# working.net
KiCad netlist of a schematic drawn in EAGLE
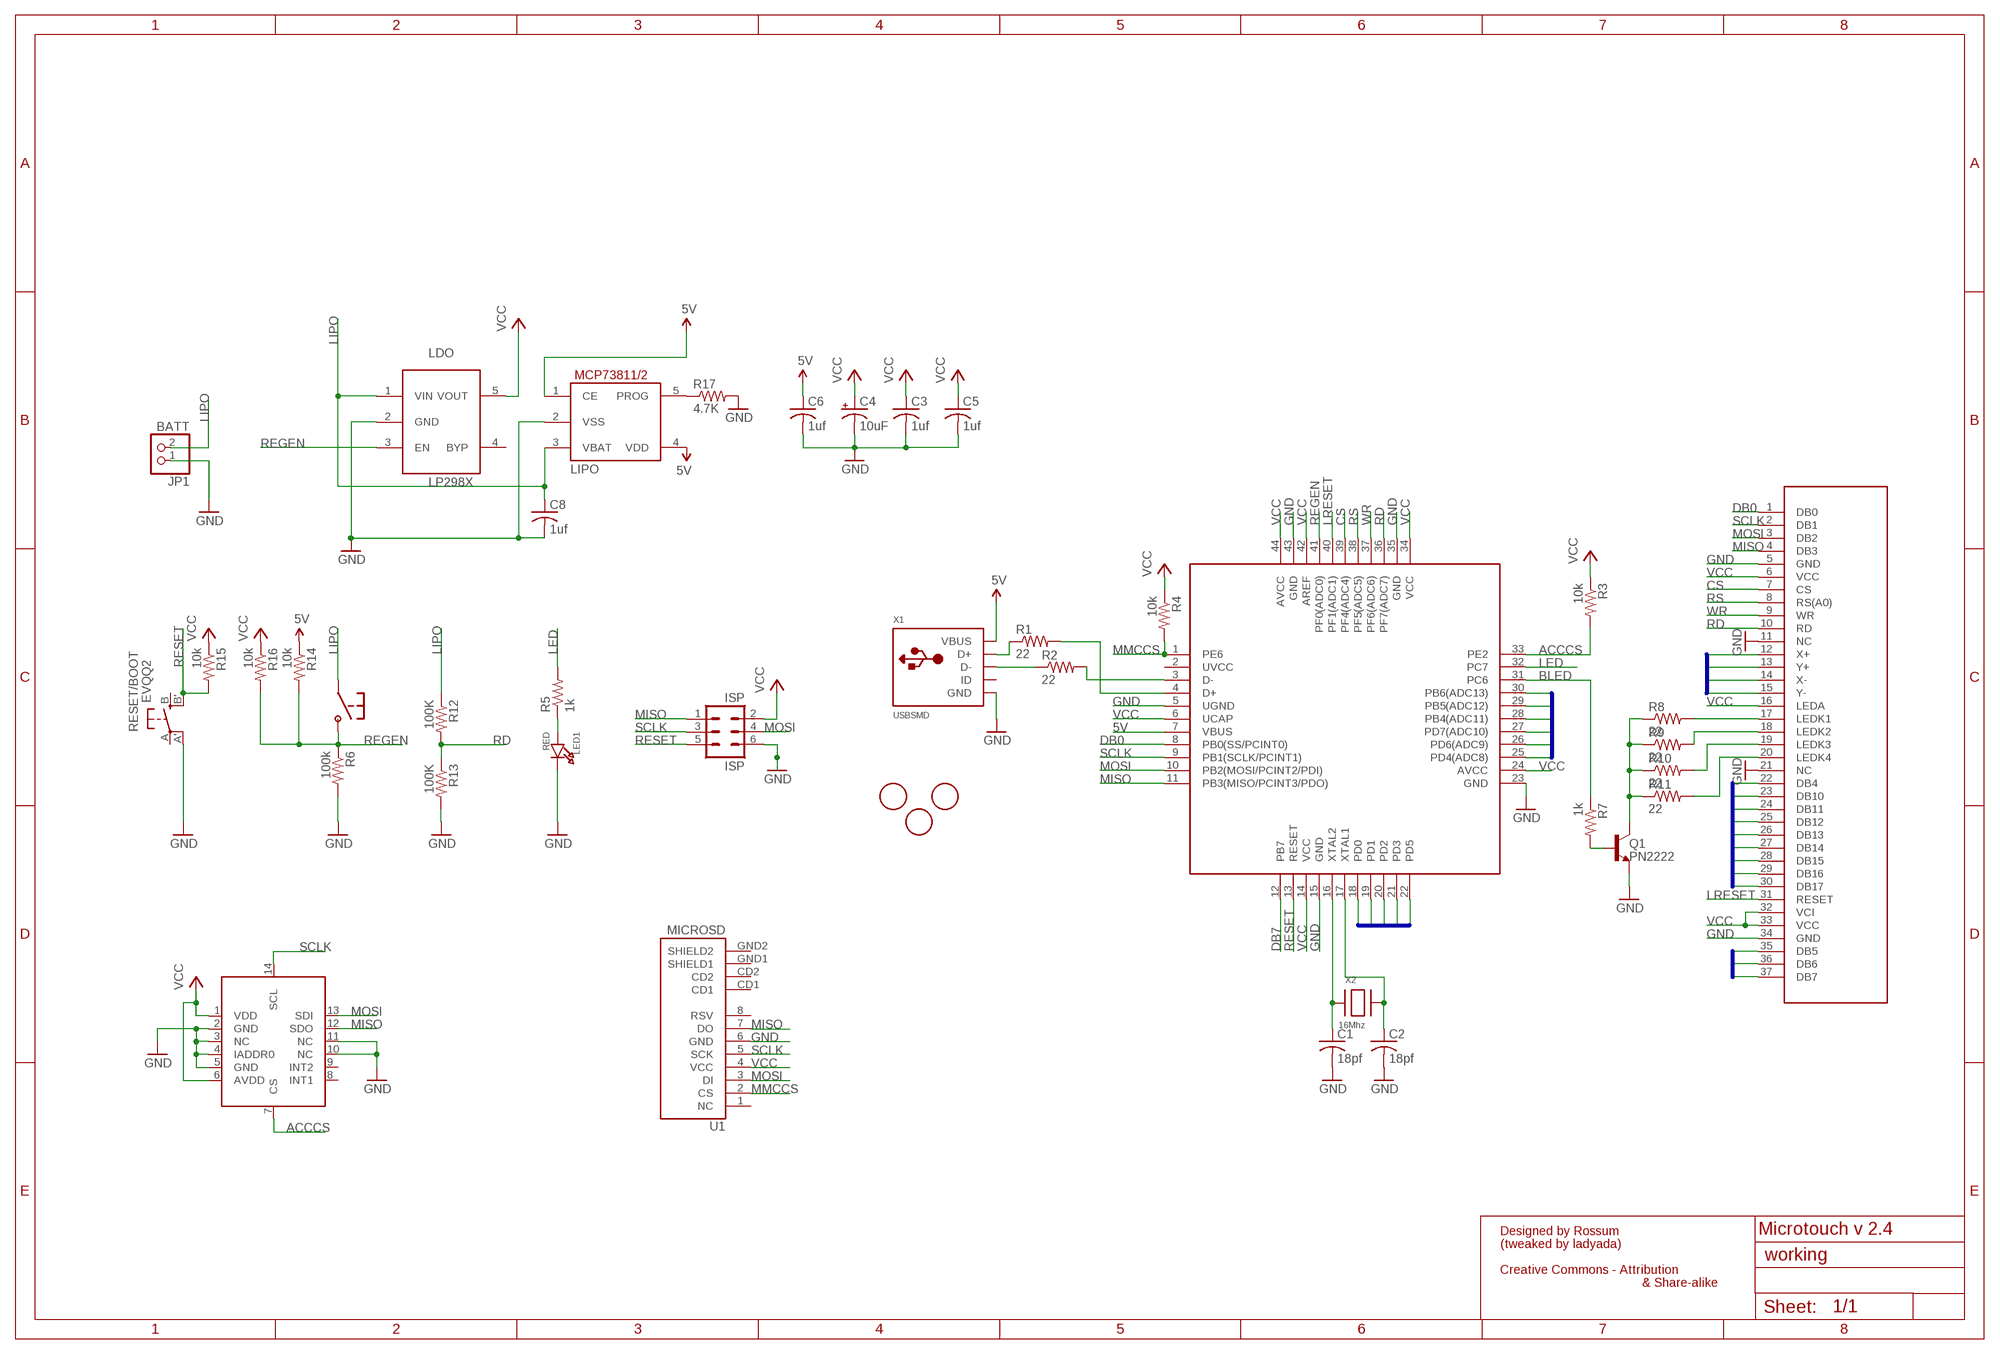
[diagram p0: schematic, sheet 1]

(export (version "E")
  (design (tool "Eeschema 10.0.6"))
  (components
    (comp (ref "ACCELEROMERTER")
      (value "MMA7455")
      (footprint "eagle-import:LGA")
      (libsource (lib "eagle-import") (part "MMA7455"))
    )
    (comp (ref "C1")
      (value "18pf")
      (footprint "eagle-import:C0805K")
      (libsource (lib "eagle-import") (part "C-USC0805K"))
    )
    (comp (ref "C2")
      (value "18pf")
      (footprint "eagle-import:C0805K")
      (libsource (lib "eagle-import") (part "C-USC0805K"))
    )
    (comp (ref "C3")
      (value "1uf")
      (footprint "eagle-import:C0805K")
      (libsource (lib "eagle-import") (part "C-USC0805K"))
    )
    (comp (ref "C4")
      (value "10uF")
      (footprint "eagle-import:A_3216-18R")
      (libsource (lib "eagle-import") (part "CPOL-USA/3216-18R"))
    )
    (comp (ref "C5")
      (value "1uf")
      (footprint "eagle-import:C0805K")
      (libsource (lib "eagle-import") (part "C-USC0805K"))
    )
    (comp (ref "C6")
      (value "1uf")
      (footprint "eagle-import:C0805K")
      (libsource (lib "eagle-import") (part "C-USC0805K"))
    )
    (comp (ref "C8")
      (value "1uf")
      (footprint "eagle-import:C0805K")
      (libsource (lib "eagle-import") (part "C-USC0805K"))
    )
    (comp (ref "ISP")
      (value "ISP")
      (footprint "eagle-import:MA03-2")
      (libsource (lib "eagle-import") (part "MA03-2"))
    )
    (comp (ref "JP1")
      (value "BATT")
      (footprint "eagle-import:JSTPH2")
      (libsource (lib "eagle-import") (part "JST_2PIN"))
    )
    (comp (ref "LDO")
      (value "LP298XS")
      (footprint "eagle-import:SOT23-5L")
      (libsource (lib "eagle-import") (part "LP298XS"))
    )
    (comp (ref "LED1")
      (value "RED")
      (footprint "eagle-import:CHIPLED_0805")
      (libsource (lib "eagle-import") (part "LED0805"))
    )
    (comp (ref "LIPO")
      (value "MCP73811/2")
      (footprint "eagle-import:SOT23-5L")
      (libsource (lib "eagle-import") (part "MCP73811/2"))
    )
    (comp (ref "Q1")
      (value "PN2222")
      (footprint "eagle-import:SOT23-BEC")
      (libsource (lib "eagle-import") (part "-NPN-SOT23-BECMMBT2222ALT1"))
    )
    (comp (ref "R1")
      (value "22")
      (footprint "eagle-import:R0805")
      (libsource (lib "eagle-import") (part "R-US_R0805"))
    )
    (comp (ref "R2")
      (value "22")
      (footprint "eagle-import:R0805")
      (libsource (lib "eagle-import") (part "R-US_R0805"))
    )
    (comp (ref "R3")
      (value "10k")
      (footprint "eagle-import:M0805")
      (libsource (lib "eagle-import") (part "R-US_M0805"))
    )
    (comp (ref "R4")
      (value "10k")
      (footprint "eagle-import:R0805")
      (libsource (lib "eagle-import") (part "R-US_R0805"))
    )
    (comp (ref "R5")
      (value "1k")
      (footprint "eagle-import:R0805")
      (libsource (lib "eagle-import") (part "R-US_R0805"))
    )
    (comp (ref "R6")
      (value "100k")
      (footprint "eagle-import:R0805")
      (libsource (lib "eagle-import") (part "R-US_R0805"))
    )
    (comp (ref "R7")
      (value "1k")
      (footprint "eagle-import:R0805")
      (libsource (lib "eagle-import") (part "R-US_R0805"))
    )
    (comp (ref "R8")
      (value "22")
      (footprint "eagle-import:R0805")
      (libsource (lib "eagle-import") (part "R-US_R0805"))
    )
    (comp (ref "R9")
      (value "22")
      (footprint "eagle-import:R0805")
      (libsource (lib "eagle-import") (part "R-US_R0805"))
    )
    (comp (ref "R10")
      (value "22")
      (footprint "eagle-import:R0805")
      (libsource (lib "eagle-import") (part "R-US_R0805"))
    )
    (comp (ref "R11")
      (value "22")
      (footprint "eagle-import:R0805")
      (libsource (lib "eagle-import") (part "R-US_R0805"))
    )
    (comp (ref "R12")
      (value "100K")
      (footprint "eagle-import:M0805")
      (libsource (lib "eagle-import") (part "R-US_M0805"))
    )
    (comp (ref "R13")
      (value "100K")
      (footprint "eagle-import:M0805")
      (libsource (lib "eagle-import") (part "R-US_M0805"))
    )
    (comp (ref "R14")
      (value "10k")
      (footprint "eagle-import:R0805")
      (libsource (lib "eagle-import") (part "R-US_R0805"))
    )
    (comp (ref "R15")
      (value "10k")
      (footprint "eagle-import:M0805")
      (libsource (lib "eagle-import") (part "R-US_M0805"))
    )
    (comp (ref "R16")
      (value "10k")
      (footprint "eagle-import:R0805")
      (libsource (lib "eagle-import") (part "R-US_R0805"))
    )
    (comp (ref "R17")
      (value "4.7K")
      (footprint "eagle-import:M0805")
      (libsource (lib "eagle-import") (part "R-US_M0805"))
    )
    (comp (ref "RESET/BOOT")
      (value "EVQQ2")
      (footprint "eagle-import:EVQ-Q2")
      (libsource (lib "eagle-import") (part "EVQQ2"))
    )
    (comp (ref "U$1")
      (value "ATMEGA32U4")
      (footprint "eagle-import:TQFP44")
      (libsource (lib "eagle-import") (part "ATMEGA32U4TQFP"))
    )
    (comp (ref "U$2")
      (value "LCD37")
      (footprint "eagle-import:LCD371MM")
      (libsource (lib "eagle-import") (part "LCD37"))
    )
    (comp (ref "U$6")
      (value "FIDUCIAL")
      (footprint "eagle-import:FIDUCIAL_1MM")
      (libsource (lib "eagle-import") (part "FIDUCIAL"))
    )
    (comp (ref "U$7")
      (value "FIDUCIAL")
      (footprint "eagle-import:FIDUCIAL_1MM")
      (libsource (lib "eagle-import") (part "FIDUCIAL"))
    )
    (comp (ref "U$8")
      (value "FIDUCIAL")
      (footprint "eagle-import:FIDUCIAL_1MM")
      (libsource (lib "eagle-import") (part "FIDUCIAL"))
    )
    (comp (ref "U1")
      (value "MICROSD")
      (footprint "eagle-import:MICRO-SD-SOCKET-PP")
      (libsource (lib "eagle-import") (part "USD-SOCKETNEW"))
    )
    (comp (ref "U2")
      (value "KSSMINISWITCH")
      (footprint "eagle-import:KSSMINI")
      (libsource (lib "eagle-import") (part "KSSMINISWITCH"))
    )
    (comp (ref "X1")
      (value "USBSMD")
      (footprint "eagle-import:USB-MINIB")
      (libsource (lib "eagle-import") (part "USBMINIB"))
    )
    (comp (ref "X2")
      (value "16Mhz")
      (footprint "eagle-import:NX5032")
      (libsource (lib "eagle-import") (part "XTALNX5032"))
    )
  )
  (nets
    (net (code "1") (name "/ACCCS") (class "Default")
      (node (ref "ACCELEROMERTER") (pin "7") (pinfunction "CS_7") (pintype "bidirectional"))
      (node (ref "R3") (pin "2") (pinfunction "2_2") (pintype "passive"))
      (node (ref "U$1") (pin "33") (pinfunction "PE2_33") (pintype "bidirectional"))
    )
    (net (code "2") (name "/BLED") (class "Default")
      (node (ref "R7") (pin "1") (pinfunction "1_1") (pintype "passive"))
      (node (ref "U$1") (pin "31") (pinfunction "PC6_31") (pintype "bidirectional"))
    )
    (net (code "3") (name "/CS") (class "Default")
      (node (ref "U$1") (pin "39") (pinfunction "PF4(ADC4)_39") (pintype "bidirectional"))
      (node (ref "U$2") (pin "7") (pinfunction "CS_7") (pintype "bidirectional"))
    )
    (net (code "4") (name "/DB0") (class "Default")
      (node (ref "U$1") (pin "8") (pinfunction "PB0(SS/PCINT0)_8") (pintype "bidirectional"))
      (node (ref "U$2") (pin "1") (pinfunction "DB0_1") (pintype "bidirectional"))
    )
    (net (code "5") (name "/DB4") (class "Default")
      (node (ref "U$1") (pin "28") (pinfunction "PB4(ADC11)_28") (pintype "bidirectional"))
      (node (ref "U$2") (pin "12") (pinfunction "X+_12") (pintype "bidirectional"))
      (node (ref "U$2") (pin "22") (pinfunction "DB4_22") (pintype "bidirectional"))
    )
    (net (code "6") (name "/DB5") (class "Default")
      (node (ref "U$1") (pin "29") (pinfunction "PB5(ADC12)_29") (pintype "bidirectional"))
      (node (ref "U$2") (pin "13") (pinfunction "Y+_13") (pintype "bidirectional"))
      (node (ref "U$2") (pin "35") (pinfunction "DB5_35") (pintype "bidirectional"))
    )
    (net (code "7") (name "/DB6") (class "Default")
      (node (ref "U$1") (pin "30") (pinfunction "PB6(ADC13)_30") (pintype "bidirectional"))
      (node (ref "U$2") (pin "36") (pinfunction "DB6_36") (pintype "bidirectional"))
    )
    (net (code "8") (name "/DB7") (class "Default")
      (node (ref "U$1") (pin "12") (pinfunction "PB7_12") (pintype "bidirectional"))
      (node (ref "U$2") (pin "37") (pinfunction "DB7_37") (pintype "bidirectional"))
    )
    (net (code "9") (name "/DB8") (class "Default")
      (node (ref "U$1") (pin "18") (pinfunction "PD0_18") (pintype "bidirectional"))
      (node (ref "U$2") (pin "23") (pinfunction "DB10_23") (pintype "bidirectional"))
    )
    (net (code "10") (name "/DB9") (class "Default")
      (node (ref "U$1") (pin "19") (pinfunction "PD1_19") (pintype "bidirectional"))
      (node (ref "U$2") (pin "24") (pinfunction "DB11_24") (pintype "bidirectional"))
    )
    (net (code "11") (name "/DB10") (class "Default")
      (node (ref "U$1") (pin "20") (pinfunction "PD2_20") (pintype "bidirectional"))
      (node (ref "U$2") (pin "25") (pinfunction "DB12_25") (pintype "bidirectional"))
    )
    (net (code "12") (name "/DB11") (class "Default")
      (node (ref "U$1") (pin "21") (pinfunction "PD3_21") (pintype "bidirectional"))
      (node (ref "U$2") (pin "26") (pinfunction "DB13_26") (pintype "bidirectional"))
    )
    (net (code "13") (name "/DB12") (class "Default")
      (node (ref "U$1") (pin "25") (pinfunction "PD4(ADC8)_25") (pintype "bidirectional"))
      (node (ref "U$2") (pin "27") (pinfunction "DB14_27") (pintype "bidirectional"))
    )
    (net (code "14") (name "/DB13") (class "Default")
      (node (ref "U$1") (pin "22") (pinfunction "PD5_22") (pintype "bidirectional"))
      (node (ref "U$2") (pin "28") (pinfunction "DB15_28") (pintype "bidirectional"))
    )
    (net (code "15") (name "/DB14") (class "Default")
      (node (ref "U$1") (pin "26") (pinfunction "PD6(ADC9)_26") (pintype "bidirectional"))
      (node (ref "U$2") (pin "14") (pinfunction "X-_14") (pintype "bidirectional"))
      (node (ref "U$2") (pin "29") (pinfunction "DB16_29") (pintype "bidirectional"))
    )
    (net (code "16") (name "/DB15") (class "Default")
      (node (ref "U$1") (pin "27") (pinfunction "PD7(ADC10)_27") (pintype "bidirectional"))
      (node (ref "U$2") (pin "15") (pinfunction "Y-_15") (pintype "bidirectional"))
      (node (ref "U$2") (pin "30") (pinfunction "DB17_30") (pintype "bidirectional"))
    )
    (net (code "17") (name "/LED") (class "Default")
      (node (ref "R5") (pin "2") (pinfunction "2_2") (pintype "passive"))
      (node (ref "U$1") (pin "32") (pinfunction "PC7_32") (pintype "bidirectional"))
    )
    (net (code "18") (name "/LIPO") (class "Default")
      (node (ref "C8") (pin "1") (pinfunction "1_1") (pintype "passive"))
      (node (ref "JP1") (pin "2") (pinfunction "2_2") (pintype "passive"))
      (node (ref "LDO") (pin "1") (pinfunction "VIN_1") (pintype "bidirectional"))
      (node (ref "LIPO") (pin "3") (pinfunction "VBAT_3") (pintype "bidirectional"))
      (node (ref "R12") (pin "1") (pinfunction "1_1") (pintype "passive"))
      (node (ref "U2") (pin "P$1") (pinfunction "P$1_P$1") (pintype "passive"))
    )
    (net (code "19") (name "/LRESET") (class "Default")
      (node (ref "U$1") (pin "40") (pinfunction "PF1(ADC1)_40") (pintype "bidirectional"))
      (node (ref "U$2") (pin "31") (pinfunction "RESET_31") (pintype "bidirectional"))
    )
    (net (code "20") (name "/MISO") (class "Default")
      (node (ref "ACCELEROMERTER") (pin "12") (pinfunction "SDO_12") (pintype "bidirectional"))
      (node (ref "ISP") (pin "1") (pinfunction "1_1") (pintype "passive"))
      (node (ref "U$1") (pin "11") (pinfunction "PB3(MISO/PCINT3/PDO)_11") (pintype "bidirectional"))
      (node (ref "U$2") (pin "4") (pinfunction "DB3_4") (pintype "bidirectional"))
      (node (ref "U1") (pin "7") (pinfunction "DO_7") (pintype "bidirectional"))
    )
    (net (code "21") (name "/MMCCS") (class "Default")
      (node (ref "R4") (pin "2") (pinfunction "2_2") (pintype "passive"))
      (node (ref "U$1") (pin "1") (pinfunction "PE6_1") (pintype "bidirectional"))
      (node (ref "U1") (pin "2") (pinfunction "CS_2") (pintype "bidirectional"))
    )
    (net (code "22") (name "/MOSI") (class "Default")
      (node (ref "ACCELEROMERTER") (pin "13") (pinfunction "SDI_13") (pintype "bidirectional"))
      (node (ref "ISP") (pin "4") (pinfunction "4_4") (pintype "passive"))
      (node (ref "U$1") (pin "10") (pinfunction "PB2(MOSI/PCINT2/PDI)_10") (pintype "bidirectional"))
      (node (ref "U$2") (pin "3") (pinfunction "DB2_3") (pintype "bidirectional"))
      (node (ref "U1") (pin "3") (pinfunction "DI_3") (pintype "bidirectional"))
    )
    (net (code "23") (name "/RD") (class "Default")
      (node (ref "R12") (pin "2") (pinfunction "2_2") (pintype "passive"))
      (node (ref "R13") (pin "1") (pinfunction "1_1") (pintype "passive"))
      (node (ref "U$1") (pin "36") (pinfunction "PF7(ADC7)_36") (pintype "bidirectional"))
      (node (ref "U$2") (pin "10") (pinfunction "RD_10") (pintype "bidirectional"))
    )
    (net (code "24") (name "/REGEN") (class "Default")
      (node (ref "LDO") (pin "3") (pinfunction "EN_3") (pintype "bidirectional"))
      (node (ref "R14") (pin "2") (pinfunction "2_2") (pintype "passive"))
      (node (ref "R16") (pin "2") (pinfunction "2_2") (pintype "passive"))
      (node (ref "R6") (pin "1") (pinfunction "1_1") (pintype "passive"))
      (node (ref "U$1") (pin "41") (pinfunction "PF0(ADC0)_41") (pintype "bidirectional"))
      (node (ref "U2") (pin "P$2") (pinfunction "P$2_P$2") (pintype "passive"))
    )
    (net (code "25") (name "/RESET") (class "Default")
      (node (ref "ISP") (pin "5") (pinfunction "5_5") (pintype "passive"))
      (node (ref "R15") (pin "2") (pinfunction "2_2") (pintype "passive"))
      (node (ref "RESET/BOOT") (pin "B'") (pinfunction "S1_B'") (pintype "passive"))
      (node (ref "U$1") (pin "13") (pinfunction "RESET_13") (pintype "bidirectional"))
    )
    (net (code "26") (name "/RS") (class "Default")
      (node (ref "U$1") (pin "38") (pinfunction "PF5(ADC5)_38") (pintype "bidirectional"))
      (node (ref "U$2") (pin "8") (pinfunction "RS(A0)_8") (pintype "bidirectional"))
    )
    (net (code "27") (name "/SCLK") (class "Default")
      (node (ref "ACCELEROMERTER") (pin "14") (pinfunction "SCL_14") (pintype "bidirectional"))
      (node (ref "ISP") (pin "3") (pinfunction "3_3") (pintype "passive"))
      (node (ref "U$1") (pin "9") (pinfunction "PB1(SCLK/PCINT1)_9") (pintype "bidirectional"))
      (node (ref "U$2") (pin "2") (pinfunction "DB1_2") (pintype "bidirectional"))
      (node (ref "U1") (pin "5") (pinfunction "SCK_5") (pintype "bidirectional"))
    )
    (net (code "28") (name "/WR") (class "Default")
      (node (ref "U$1") (pin "37") (pinfunction "PF6(ADC6)_37") (pintype "bidirectional"))
      (node (ref "U$2") (pin "9") (pinfunction "WR_9") (pintype "bidirectional"))
    )
    (net (code "29") (name "5V") (class "Default")
      (node (ref "C6") (pin "1") (pinfunction "1_1") (pintype "passive"))
      (node (ref "LIPO") (pin "1") (pinfunction "CE_1") (pintype "input"))
      (node (ref "LIPO") (pin "4") (pinfunction "VDD_4") (pintype "power_in"))
      (node (ref "R14") (pin "1") (pinfunction "1_1") (pintype "passive"))
      (node (ref "U$1") (pin "7") (pinfunction "VBUS_7") (pintype "bidirectional"))
      (node (ref "X1") (pin "VBUS") (pinfunction "VBUS_VBUS") (pintype "power_in"))
    )
    (net (code "30") (name "GND") (class "Default")
      (node (ref "ACCELEROMERTER") (pin "10") (pinfunction "NC_10") (pintype "bidirectional"))
      (node (ref "ACCELEROMERTER") (pin "11") (pinfunction "NC_11") (pintype "bidirectional"))
      (node (ref "ACCELEROMERTER") (pin "2") (pinfunction "GND_2") (pintype "bidirectional"))
      (node (ref "ACCELEROMERTER") (pin "3") (pinfunction "NC_3") (pintype "bidirectional"))
      (node (ref "ACCELEROMERTER") (pin "4") (pinfunction "IADDR0_4") (pintype "bidirectional"))
      (node (ref "ACCELEROMERTER") (pin "5") (pinfunction "GND_5") (pintype "bidirectional"))
      (node (ref "C1") (pin "2") (pinfunction "2_2") (pintype "passive"))
      (node (ref "C2") (pin "2") (pinfunction "2_2") (pintype "passive"))
      (node (ref "C3") (pin "2") (pinfunction "2_2") (pintype "passive"))
      (node (ref "C4") (pin "-") (pinfunction "-_-") (pintype "passive"))
      (node (ref "C5") (pin "2") (pinfunction "2_2") (pintype "passive"))
      (node (ref "C6") (pin "2") (pinfunction "2_2") (pintype "passive"))
      (node (ref "C8") (pin "2") (pinfunction "2_2") (pintype "passive"))
      (node (ref "ISP") (pin "6") (pinfunction "6_6") (pintype "passive"))
      (node (ref "JP1") (pin "1") (pinfunction "1_1") (pintype "passive"))
      (node (ref "LDO") (pin "2") (pinfunction "GND_2") (pintype "bidirectional"))
      (node (ref "LED1") (pin "C") (pinfunction "C_C") (pintype "passive"))
      (node (ref "LIPO") (pin "2") (pinfunction "VSS_2") (pintype "power_in"))
      (node (ref "Q1") (pin "E") (pinfunction "E_E") (pintype "passive"))
      (node (ref "R13") (pin "2") (pinfunction "2_2") (pintype "passive"))
      (node (ref "R17") (pin "2") (pinfunction "2_2") (pintype "passive"))
      (node (ref "R6") (pin "2") (pinfunction "2_2") (pintype "passive"))
      (node (ref "RESET/BOOT") (pin "A'") (pinfunction "P1_A'") (pintype "passive"))
      (node (ref "U$1") (pin "15") (pinfunction "GND_15") (pintype "bidirectional"))
      (node (ref "U$1") (pin "23") (pinfunction "GND_23") (pintype "bidirectional"))
      (node (ref "U$1") (pin "35") (pinfunction "GND_35") (pintype "bidirectional"))
      (node (ref "U$1") (pin "43") (pinfunction "GND_43") (pintype "bidirectional"))
      (node (ref "U$1") (pin "5") (pinfunction "UGND_5") (pintype "bidirectional"))
      (node (ref "U$2") (pin "11") (pinfunction "NC_11") (pintype "bidirectional"))
      (node (ref "U$2") (pin "21") (pinfunction "NC_21") (pintype "bidirectional"))
      (node (ref "U$2") (pin "34") (pinfunction "GND_34") (pintype "bidirectional"))
      (node (ref "U$2") (pin "5") (pinfunction "GND_5") (pintype "bidirectional"))
      (node (ref "U1") (pin "6") (pinfunction "GND_6") (pintype "bidirectional"))
      (node (ref "X1") (pin "GND") (pinfunction "GND_GND") (pintype "power_in"))
    )
    (net (code "31") (name "Net-(LED1-PadA)") (class "Default")
      (node (ref "LED1") (pin "A") (pinfunction "A_A") (pintype "passive"))
      (node (ref "R5") (pin "1") (pinfunction "1_1") (pintype "passive"))
    )
    (net (code "32") (name "Net-(LIPO-PROG)") (class "Default")
      (node (ref "LIPO") (pin "5") (pinfunction "PROG_5") (pintype "input"))
      (node (ref "R17") (pin "1") (pinfunction "1_1") (pintype "passive"))
    )
    (net (code "33") (name "Net-(Q1-PadB)") (class "Default")
      (node (ref "Q1") (pin "B") (pinfunction "B_B") (pintype "passive"))
      (node (ref "R7") (pin "2") (pinfunction "2_2") (pintype "passive"))
    )
    (net (code "34") (name "Net-(Q1-PadC)") (class "Default")
      (node (ref "Q1") (pin "C") (pinfunction "C_C") (pintype "passive"))
      (node (ref "R10") (pin "1") (pinfunction "1_1") (pintype "passive"))
      (node (ref "R11") (pin "1") (pinfunction "1_1") (pintype "passive"))
      (node (ref "R8") (pin "1") (pinfunction "1_1") (pintype "passive"))
      (node (ref "R9") (pin "1") (pinfunction "1_1") (pintype "passive"))
    )
    (net (code "35") (name "Net-(R1-Pad1)") (class "Default")
      (node (ref "R1") (pin "1") (pinfunction "1_1") (pintype "passive"))
      (node (ref "X1") (pin "D+") (pinfunction "D+_D+") (pintype "bidirectional"))
    )
    (net (code "36") (name "Net-(R2-Pad1)") (class "Default")
      (node (ref "R2") (pin "1") (pinfunction "1_1") (pintype "passive"))
      (node (ref "X1") (pin "D-") (pinfunction "D-_D-") (pintype "bidirectional"))
    )
    (net (code "37") (name "Net-(U$1-D+)") (class "Default")
      (node (ref "R1") (pin "2") (pinfunction "2_2") (pintype "passive"))
      (node (ref "U$1") (pin "4") (pinfunction "D+_4") (pintype "bidirectional"))
    )
    (net (code "38") (name "Net-(U$1-D-)") (class "Default")
      (node (ref "R2") (pin "2") (pinfunction "2_2") (pintype "passive"))
      (node (ref "U$1") (pin "3") (pinfunction "D-_3") (pintype "bidirectional"))
    )
    (net (code "39") (name "Net-(U$1-XTAL1)") (class "Default")
      (node (ref "C2") (pin "1") (pinfunction "1_1") (pintype "passive"))
      (node (ref "U$1") (pin "17") (pinfunction "XTAL1_17") (pintype "bidirectional"))
      (node (ref "X2") (pin "P$2") (pinfunction "P$2_P$2") (pintype "bidirectional"))
    )
    (net (code "40") (name "Net-(U$1-XTAL2)") (class "Default")
      (node (ref "C1") (pin "1") (pinfunction "1_1") (pintype "passive"))
      (node (ref "U$1") (pin "16") (pinfunction "XTAL2_16") (pintype "bidirectional"))
      (node (ref "X2") (pin "P$1") (pinfunction "P$1_P$1") (pintype "bidirectional"))
    )
    (net (code "41") (name "Net-(U$2-LEDK1)") (class "Default")
      (node (ref "R8") (pin "2") (pinfunction "2_2") (pintype "passive"))
      (node (ref "U$2") (pin "17") (pinfunction "LEDK1_17") (pintype "bidirectional"))
    )
    (net (code "42") (name "Net-(U$2-LEDK2)") (class "Default")
      (node (ref "R9") (pin "2") (pinfunction "2_2") (pintype "passive"))
      (node (ref "U$2") (pin "18") (pinfunction "LEDK2_18") (pintype "bidirectional"))
    )
    (net (code "43") (name "Net-(U$2-LEDK3)") (class "Default")
      (node (ref "R10") (pin "2") (pinfunction "2_2") (pintype "passive"))
      (node (ref "U$2") (pin "19") (pinfunction "LEDK3_19") (pintype "bidirectional"))
    )
    (net (code "44") (name "Net-(U$2-LEDK4)") (class "Default")
      (node (ref "R11") (pin "2") (pinfunction "2_2") (pintype "passive"))
      (node (ref "U$2") (pin "20") (pinfunction "LEDK4_20") (pintype "bidirectional"))
    )
    (net (code "45") (name "VCC") (class "Default")
      (node (ref "ACCELEROMERTER") (pin "1") (pinfunction "VDD_1") (pintype "bidirectional"))
      (node (ref "ACCELEROMERTER") (pin "6") (pinfunction "AVDD_6") (pintype "bidirectional"))
      (node (ref "C3") (pin "1") (pinfunction "1_1") (pintype "passive"))
      (node (ref "C4") (pin "+") (pinfunction "+_+") (pintype "passive"))
      (node (ref "C5") (pin "1") (pinfunction "1_1") (pintype "passive"))
      (node (ref "ISP") (pin "2") (pinfunction "2_2") (pintype "passive"))
      (node (ref "LDO") (pin "5") (pinfunction "VOUT_5") (pintype "bidirectional"))
      (node (ref "R15") (pin "1") (pinfunction "1_1") (pintype "passive"))
      (node (ref "R16") (pin "1") (pinfunction "1_1") (pintype "passive"))
      (node (ref "R3") (pin "1") (pinfunction "1_1") (pintype "passive"))
      (node (ref "R4") (pin "1") (pinfunction "1_1") (pintype "passive"))
      (node (ref "U$1") (pin "14") (pinfunction "VCC_14") (pintype "bidirectional"))
      (node (ref "U$1") (pin "24") (pinfunction "AVCC_24") (pintype "bidirectional"))
      (node (ref "U$1") (pin "34") (pinfunction "VCC_34") (pintype "power_in"))
      (node (ref "U$1") (pin "42") (pinfunction "AREF_42") (pintype "bidirectional"))
      (node (ref "U$1") (pin "44") (pinfunction "AVCC_44") (pintype "bidirectional"))
      (node (ref "U$1") (pin "6") (pinfunction "UCAP_6") (pintype "bidirectional"))
      (node (ref "U$2") (pin "16") (pinfunction "LEDA_16") (pintype "bidirectional"))
      (node (ref "U$2") (pin "32") (pinfunction "VCI_32") (pintype "bidirectional"))
      (node (ref "U$2") (pin "33") (pinfunction "VCC_33") (pintype "bidirectional"))
      (node (ref "U$2") (pin "6") (pinfunction "VCC_6") (pintype "bidirectional"))
      (node (ref "U1") (pin "4") (pinfunction "VCC_4") (pintype "bidirectional"))
    )
    (net (code "46") (name "unconnected-(ACCELEROMERTER-INT1-Pad8)") (class "Default")
      (node (ref "ACCELEROMERTER") (pin "8") (pinfunction "INT1_8") (pintype "bidirectional"))
    )
    (net (code "47") (name "unconnected-(ACCELEROMERTER-INT2-Pad9)") (class "Default")
      (node (ref "ACCELEROMERTER") (pin "9") (pinfunction "INT2_9") (pintype "bidirectional"))
    )
    (net (code "48") (name "unconnected-(LDO-BYP-Pad4)") (class "Default")
      (node (ref "LDO") (pin "4") (pinfunction "BYP_4") (pintype "bidirectional"))
    )
    (net (code "49") (name "unconnected-(RESET/BOOT-P-PadA)") (class "Default")
      (node (ref "RESET/BOOT") (pin "A") (pinfunction "P_A") (pintype "passive"))
    )
    (net (code "50") (name "unconnected-(RESET/BOOT-S-PadB)") (class "Default")
      (node (ref "RESET/BOOT") (pin "B") (pinfunction "S_B") (pintype "passive"))
    )
    (net (code "51") (name "unconnected-(U$1-UVCC-Pad2)") (class "Default")
      (node (ref "U$1") (pin "2") (pinfunction "UVCC_2") (pintype "bidirectional"))
    )
    (net (code "52") (name "unconnected-(U1-NC-Pad1)") (class "Default")
      (node (ref "U1") (pin "1") (pinfunction "NC_1") (pintype "bidirectional"))
    )
    (net (code "53") (name "unconnected-(U1-PadCD1)") (class "Default")
      (node (ref "U1") (pin "CD1") (pinfunction "CD1_CD1") (pintype "bidirectional"))
    )
    (net (code "54") (name "unconnected-(U1-PadCD2)") (class "Default")
      (node (ref "U1") (pin "CD2") (pinfunction "CD2_CD2") (pintype "bidirectional"))
    )
    (net (code "55") (name "unconnected-(U1-RSV-Pad8)") (class "Default")
      (node (ref "U1") (pin "8") (pinfunction "RSV_8") (pintype "bidirectional"))
    )
    (net (code "56") (name "unconnected-(U1-SHIELD1-PadGND1)") (class "Default")
      (node (ref "U1") (pin "GND1") (pinfunction "SHIELD1_GND1") (pintype "bidirectional"))
    )
    (net (code "57") (name "unconnected-(U1-SHIELD2-PadGND2)") (class "Default")
      (node (ref "U1") (pin "GND2") (pinfunction "SHIELD2_GND2") (pintype "bidirectional"))
    )
    (net (code "58") (name "unconnected-(X1-PadID)") (class "Default")
      (node (ref "X1") (pin "ID") (pinfunction "ID_ID") (pintype "bidirectional"))
    )
  )
)
